# 03_Peripheral.net
KiCad netlist of a schematic drawn in Altium Designer
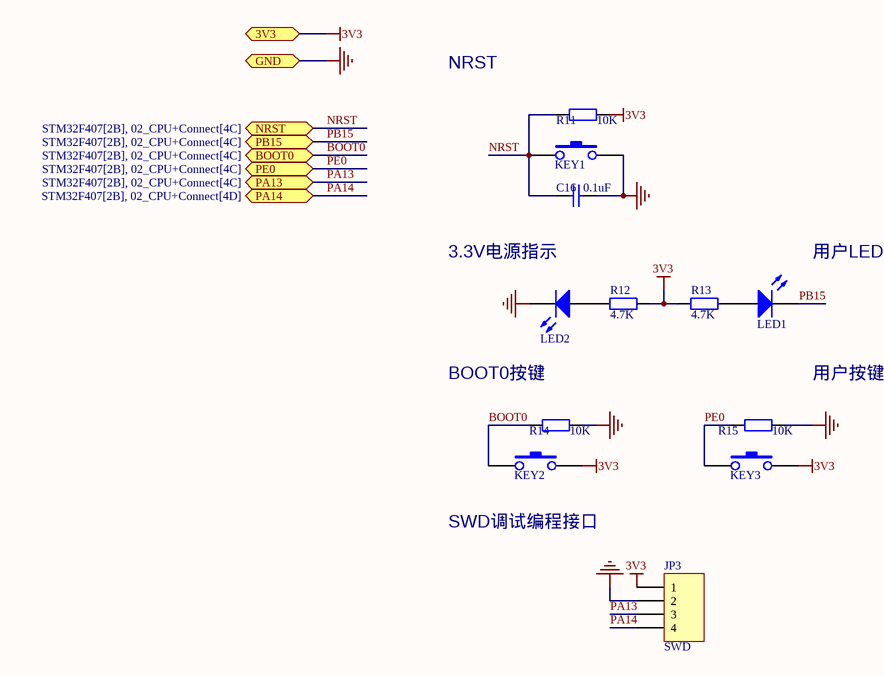
[diagram p0: 03_Peripheral.SchDoc]

(export (version "E")
  (design (tool "Eeschema 10.0.6"))
  (components
    (comp (ref "C16") (value "0.1uF") (footprint "C 0402_L") (libsource (lib "Schlib1") (part "Cap")))
    (comp (ref "JP3")
      (value "SWD")
      (footprint "HDR2.54-WS-4P")
      (fields (field (name "PUBLISHER") "Altium Limited"))
      (libsource (lib "Schlib1") (part "Header 1*4"))
    )
    (comp (ref "KEY1") (value "KEY") (footprint "SWT3*4") (libsource (lib "Schlib1") (part "KEY")))
    (comp (ref "KEY2") (value "KEY") (footprint "SWT3*4") (libsource (lib "Schlib1") (part "KEY")))
    (comp (ref "KEY3") (value "KEY") (footprint "SWT3*4") (libsource (lib "Schlib1") (part "KEY")))
    (comp (ref "LED1") (value "LED") (footprint "LED 0603") (libsource (lib "Schlib1") (part "LED")))
    (comp (ref "LED2") (value "LED") (footprint "LED 0603") (libsource (lib "Schlib1") (part "LED")))
    (comp (ref "R11") (value "10K") (footprint "R 0402_L") (libsource (lib "") (part "Res_1")))
    (comp (ref "R12") (value "4.7K") (footprint "R 0402_L") (libsource (lib "") (part "Res_1")))
    (comp (ref "R13") (value "4.7K") (footprint "R 0402_L") (libsource (lib "Schlib1") (part "Res")))
    (comp (ref "R14") (value "10K") (footprint "R 0402_L") (libsource (lib "") (part "Res_1")))
    (comp (ref "R15") (value "10K") (footprint "R 0402_L") (libsource (lib "") (part "Res_1")))
  )
  (nets
    (net (code "1") (name "/BOOT0") (class "Default")
      (node (ref "KEY2") (pin "1") (pinfunction "1_1") (pintype "passive"))
      (node (ref "R14") (pin "2") (pinfunction "2_2") (pintype "passive"))
    )
    (net (code "2") (name "/NRST") (class "Default")
      (node (ref "C16") (pin "2") (pinfunction "2_2") (pintype "passive"))
      (node (ref "KEY1") (pin "1") (pinfunction "1_1") (pintype "passive"))
      (node (ref "R11") (pin "2") (pinfunction "2_2") (pintype "passive"))
    )
    (net (code "3") (name "/PA13") (class "Default")
      (node (ref "JP3") (pin "3") (pinfunction "3_3") (pintype "passive"))
    )
    (net (code "4") (name "/PA14") (class "Default")
      (node (ref "JP3") (pin "4") (pinfunction "4_4") (pintype "passive"))
    )
    (net (code "5") (name "/PB15") (class "Default")
      (node (ref "LED1") (pin "2") (pinfunction "K_2") (pintype "passive"))
    )
    (net (code "6") (name "/PE0") (class "Default")
      (node (ref "KEY3") (pin "1") (pinfunction "1_1") (pintype "passive"))
      (node (ref "R15") (pin "2") (pinfunction "2_2") (pintype "passive"))
    )
    (net (code "7") (name "3V3") (class "Default")
      (node (ref "JP3") (pin "1") (pinfunction "1_1") (pintype "passive"))
      (node (ref "KEY2") (pin "2") (pinfunction "2_2") (pintype "passive"))
      (node (ref "KEY3") (pin "2") (pinfunction "2_2") (pintype "passive"))
      (node (ref "R11") (pin "1") (pinfunction "1_1") (pintype "passive"))
      (node (ref "R12") (pin "1") (pinfunction "1_1") (pintype "passive"))
      (node (ref "R13") (pin "1") (pinfunction "1_1") (pintype "passive"))
    )
    (net (code "8") (name "GND") (class "Default")
      (node (ref "C16") (pin "1") (pinfunction "1_1") (pintype "passive"))
      (node (ref "JP3") (pin "2") (pinfunction "2_2") (pintype "passive"))
      (node (ref "KEY1") (pin "2") (pinfunction "2_2") (pintype "passive"))
      (node (ref "LED2") (pin "2") (pinfunction "K_2") (pintype "passive"))
      (node (ref "R14") (pin "1") (pinfunction "1_1") (pintype "passive"))
      (node (ref "R15") (pin "1") (pinfunction "1_1") (pintype "passive"))
    )
    (net (code "9") (name "Net-(LED1-A)") (class "Default")
      (node (ref "LED1") (pin "1") (pinfunction "A_1") (pintype "passive"))
      (node (ref "R13") (pin "2") (pinfunction "2_2") (pintype "passive"))
    )
    (net (code "10") (name "Net-(LED2-A)") (class "Default")
      (node (ref "LED2") (pin "1") (pinfunction "A_1") (pintype "passive"))
      (node (ref "R12") (pin "2") (pinfunction "2_2") (pintype "passive"))
    )
  )
)
